# McPiFace-Camera-V1.net
KiCad netlist of a schematic drawn in EAGLE
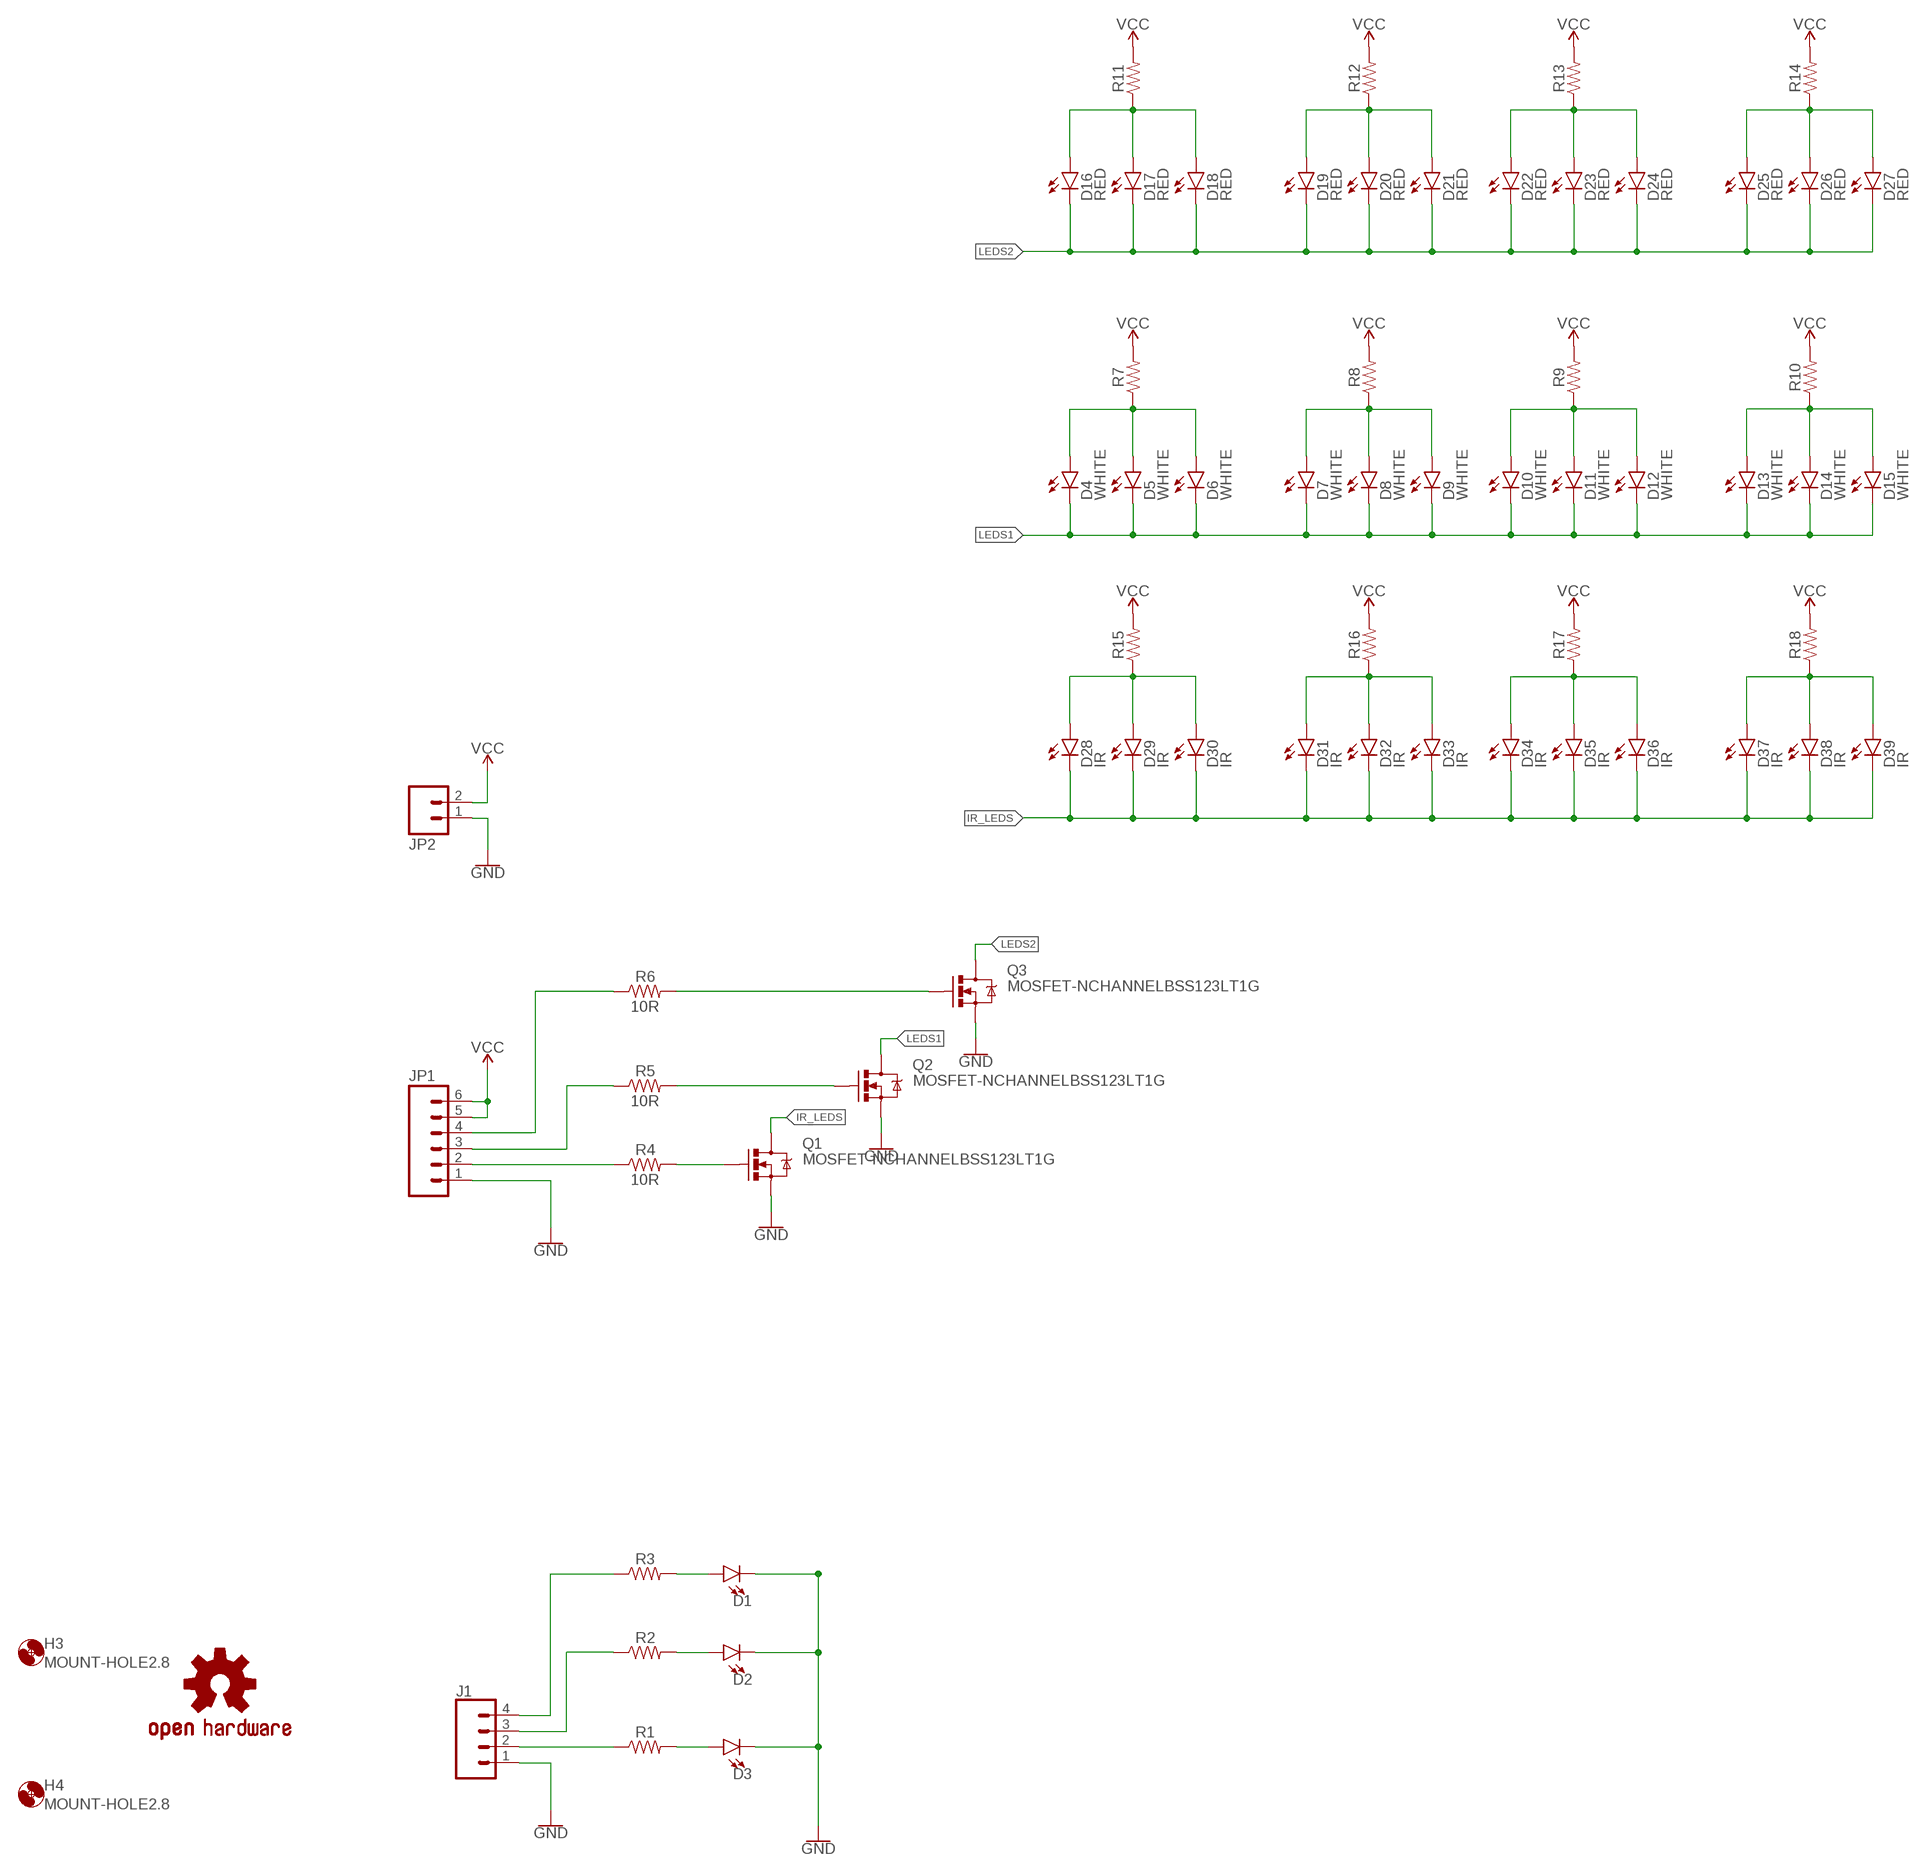
[diagram p0: schematic, sheet 1]

(export (version "E")
  (design (tool "Eeschema 10.0.6"))
  (components
    (comp (ref "D1")
      (value "LED1206-BOTTOM-1.6MM")
      (footprint "eagle-import:LED-1206-BOTTOM-1.6MM")
      (libsource (lib "eagle-import") (part "LED1206-BOTTOM-1.6MM"))
    )
    (comp (ref "D2")
      (value "LED1206-BOTTOM-1.6MM")
      (footprint "eagle-import:LED-1206-BOTTOM-1.6MM")
      (libsource (lib "eagle-import") (part "LED1206-BOTTOM-1.6MM"))
    )
    (comp (ref "D3")
      (value "LED1206-BOTTOM-1.6MM")
      (footprint "eagle-import:LED-1206-BOTTOM-1.6MM")
      (libsource (lib "eagle-import") (part "LED1206-BOTTOM-1.6MM"))
    )
    (comp (ref "D4")
      (value "WHITE")
      (footprint "eagle-import:LED-1206")
      (libsource (lib "eagle-import") (part "LED-WHITE1206"))
    )
    (comp (ref "D5")
      (value "WHITE")
      (footprint "eagle-import:LED-1206")
      (libsource (lib "eagle-import") (part "LED-WHITE1206"))
    )
    (comp (ref "D6")
      (value "WHITE")
      (footprint "eagle-import:LED-1206")
      (libsource (lib "eagle-import") (part "LED-WHITE1206"))
    )
    (comp (ref "D7")
      (value "WHITE")
      (footprint "eagle-import:LED-1206")
      (libsource (lib "eagle-import") (part "LED-WHITE1206"))
    )
    (comp (ref "D8")
      (value "WHITE")
      (footprint "eagle-import:LED-1206")
      (libsource (lib "eagle-import") (part "LED-WHITE1206"))
    )
    (comp (ref "D9")
      (value "WHITE")
      (footprint "eagle-import:LED-1206")
      (libsource (lib "eagle-import") (part "LED-WHITE1206"))
    )
    (comp (ref "D10")
      (value "WHITE")
      (footprint "eagle-import:LED-1206")
      (libsource (lib "eagle-import") (part "LED-WHITE1206"))
    )
    (comp (ref "D11")
      (value "WHITE")
      (footprint "eagle-import:LED-1206")
      (libsource (lib "eagle-import") (part "LED-WHITE1206"))
    )
    (comp (ref "D12")
      (value "WHITE")
      (footprint "eagle-import:LED-1206")
      (libsource (lib "eagle-import") (part "LED-WHITE1206"))
    )
    (comp (ref "D13")
      (value "WHITE")
      (footprint "eagle-import:LED-1206")
      (libsource (lib "eagle-import") (part "LED-WHITE1206"))
    )
    (comp (ref "D14")
      (value "WHITE")
      (footprint "eagle-import:LED-1206")
      (libsource (lib "eagle-import") (part "LED-WHITE1206"))
    )
    (comp (ref "D15")
      (value "WHITE")
      (footprint "eagle-import:LED-1206")
      (libsource (lib "eagle-import") (part "LED-WHITE1206"))
    )
    (comp (ref "D16")
      (value "RED")
      (footprint "eagle-import:LED-1206")
      (libsource (lib "eagle-import") (part "LED-RED1206"))
    )
    (comp (ref "D17")
      (value "RED")
      (footprint "eagle-import:LED-1206")
      (libsource (lib "eagle-import") (part "LED-RED1206"))
    )
    (comp (ref "D18")
      (value "RED")
      (footprint "eagle-import:LED-1206")
      (libsource (lib "eagle-import") (part "LED-RED1206"))
    )
    (comp (ref "D19")
      (value "RED")
      (footprint "eagle-import:LED-1206")
      (libsource (lib "eagle-import") (part "LED-RED1206"))
    )
    (comp (ref "D20")
      (value "RED")
      (footprint "eagle-import:LED-1206")
      (libsource (lib "eagle-import") (part "LED-RED1206"))
    )
    (comp (ref "D21")
      (value "RED")
      (footprint "eagle-import:LED-1206")
      (libsource (lib "eagle-import") (part "LED-RED1206"))
    )
    (comp (ref "D22")
      (value "RED")
      (footprint "eagle-import:LED-1206")
      (libsource (lib "eagle-import") (part "LED-RED1206"))
    )
    (comp (ref "D23")
      (value "RED")
      (footprint "eagle-import:LED-1206")
      (libsource (lib "eagle-import") (part "LED-RED1206"))
    )
    (comp (ref "D24")
      (value "RED")
      (footprint "eagle-import:LED-1206")
      (libsource (lib "eagle-import") (part "LED-RED1206"))
    )
    (comp (ref "D25")
      (value "RED")
      (footprint "eagle-import:LED-1206")
      (libsource (lib "eagle-import") (part "LED-RED1206"))
    )
    (comp (ref "D26")
      (value "RED")
      (footprint "eagle-import:LED-1206")
      (libsource (lib "eagle-import") (part "LED-RED1206"))
    )
    (comp (ref "D27")
      (value "RED")
      (footprint "eagle-import:LED-1206")
      (libsource (lib "eagle-import") (part "LED-RED1206"))
    )
    (comp (ref "D28")
      (value "IR")
      (footprint "eagle-import:LED-1206")
      (libsource (lib "eagle-import") (part "LED1206"))
    )
    (comp (ref "D29")
      (value "IR")
      (footprint "eagle-import:LED-1206")
      (libsource (lib "eagle-import") (part "LED1206"))
    )
    (comp (ref "D30")
      (value "IR")
      (footprint "eagle-import:LED-1206")
      (libsource (lib "eagle-import") (part "LED1206"))
    )
    (comp (ref "D31")
      (value "IR")
      (footprint "eagle-import:LED-1206")
      (libsource (lib "eagle-import") (part "LED1206"))
    )
    (comp (ref "D32")
      (value "IR")
      (footprint "eagle-import:LED-1206")
      (libsource (lib "eagle-import") (part "LED1206"))
    )
    (comp (ref "D33")
      (value "IR")
      (footprint "eagle-import:LED-1206")
      (libsource (lib "eagle-import") (part "LED1206"))
    )
    (comp (ref "D34")
      (value "IR")
      (footprint "eagle-import:LED-1206")
      (libsource (lib "eagle-import") (part "LED1206"))
    )
    (comp (ref "D35")
      (value "IR")
      (footprint "eagle-import:LED-1206")
      (libsource (lib "eagle-import") (part "LED1206"))
    )
    (comp (ref "D36")
      (value "IR")
      (footprint "eagle-import:LED-1206")
      (libsource (lib "eagle-import") (part "LED1206"))
    )
    (comp (ref "D37")
      (value "IR")
      (footprint "eagle-import:LED-1206")
      (libsource (lib "eagle-import") (part "LED1206"))
    )
    (comp (ref "D38")
      (value "IR")
      (footprint "eagle-import:LED-1206")
      (libsource (lib "eagle-import") (part "LED1206"))
    )
    (comp (ref "D39")
      (value "IR")
      (footprint "eagle-import:LED-1206")
      (libsource (lib "eagle-import") (part "LED1206"))
    )
    (comp (ref "H3")
      (value "MOUNT-HOLE2.8")
      (footprint "eagle-import:2,8")
      (libsource (lib "eagle-import") (part "MOUNT-HOLE2.8"))
    )
    (comp (ref "H4")
      (value "MOUNT-HOLE2.8")
      (footprint "eagle-import:2,8")
      (libsource (lib "eagle-import") (part "MOUNT-HOLE2.8"))
    )
    (comp (ref "J1")
      (value "CONN_04SMD2")
      (footprint "eagle-import:1X04_1MM_RA")
      (libsource (lib "eagle-import") (part "CONN_04SMD2"))
    )
    (comp (ref "JP1")
      (value "M06SMD-1MM")
      (footprint "eagle-import:1X06-1MM")
      (libsource (lib "eagle-import") (part "M06SMD-1MM"))
    )
    (comp (ref "JP2")
      (value "M02-JST-2MM-SMT")
      (footprint "eagle-import:JST-2-SMD")
      (libsource (lib "eagle-import") (part "M02-JST-2MM-SMT"))
    )
    (comp (ref "LOGO1")
      (value "OSHW-LOGOL")
      (footprint "eagle-import:OSHW-LOGO-L")
      (libsource (lib "eagle-import") (part "OSHW-LOGOL"))
    )
    (comp (ref "Q1")
      (value "MOSFET-NCHANNELBSS123LT1G")
      (footprint "eagle-import:SOT23-3")
      (libsource (lib "eagle-import") (part "MOSFET-NCHANNELBSS123LT1G"))
    )
    (comp (ref "Q2")
      (value "MOSFET-NCHANNELBSS123LT1G")
      (footprint "eagle-import:SOT23-3")
      (libsource (lib "eagle-import") (part "MOSFET-NCHANNELBSS123LT1G"))
    )
    (comp (ref "Q3")
      (value "MOSFET-NCHANNELBSS123LT1G")
      (footprint "eagle-import:SOT23-3")
      (libsource (lib "eagle-import") (part "MOSFET-NCHANNELBSS123LT1G"))
    )
    (comp (ref "R1")
      (value "RESISTOR1206")
      (footprint "eagle-import:1206")
      (libsource (lib "eagle-import") (part "RESISTOR1206"))
    )
    (comp (ref "R2")
      (value "RESISTOR1206")
      (footprint "eagle-import:1206")
      (libsource (lib "eagle-import") (part "RESISTOR1206"))
    )
    (comp (ref "R3")
      (value "RESISTOR1206")
      (footprint "eagle-import:1206")
      (libsource (lib "eagle-import") (part "RESISTOR1206"))
    )
    (comp (ref "R4")
      (value "10R")
      (footprint "eagle-import:1206")
      (libsource (lib "eagle-import") (part "RESISTOR1206"))
    )
    (comp (ref "R5")
      (value "10R")
      (footprint "eagle-import:1206")
      (libsource (lib "eagle-import") (part "RESISTOR1206"))
    )
    (comp (ref "R6")
      (value "10R")
      (footprint "eagle-import:1206")
      (libsource (lib "eagle-import") (part "RESISTOR1206"))
    )
    (comp (ref "R7")
      (value "RESISTOR1206")
      (footprint "eagle-import:1206")
      (libsource (lib "eagle-import") (part "RESISTOR1206"))
    )
    (comp (ref "R8")
      (value "RESISTOR1206")
      (footprint "eagle-import:1206")
      (libsource (lib "eagle-import") (part "RESISTOR1206"))
    )
    (comp (ref "R9")
      (value "RESISTOR1206")
      (footprint "eagle-import:1206")
      (libsource (lib "eagle-import") (part "RESISTOR1206"))
    )
    (comp (ref "R10")
      (value "RESISTOR1206")
      (footprint "eagle-import:1206")
      (libsource (lib "eagle-import") (part "RESISTOR1206"))
    )
    (comp (ref "R11")
      (value "RESISTOR1206")
      (footprint "eagle-import:1206")
      (libsource (lib "eagle-import") (part "RESISTOR1206"))
    )
    (comp (ref "R12")
      (value "RESISTOR1206")
      (footprint "eagle-import:1206")
      (libsource (lib "eagle-import") (part "RESISTOR1206"))
    )
    (comp (ref "R13")
      (value "RESISTOR1206")
      (footprint "eagle-import:1206")
      (libsource (lib "eagle-import") (part "RESISTOR1206"))
    )
    (comp (ref "R14")
      (value "RESISTOR1206")
      (footprint "eagle-import:1206")
      (libsource (lib "eagle-import") (part "RESISTOR1206"))
    )
    (comp (ref "R15")
      (value "RESISTOR1206")
      (footprint "eagle-import:1206")
      (libsource (lib "eagle-import") (part "RESISTOR1206"))
    )
    (comp (ref "R16")
      (value "RESISTOR1206")
      (footprint "eagle-import:1206")
      (libsource (lib "eagle-import") (part "RESISTOR1206"))
    )
    (comp (ref "R17")
      (value "RESISTOR1206")
      (footprint "eagle-import:1206")
      (libsource (lib "eagle-import") (part "RESISTOR1206"))
    )
    (comp (ref "R18")
      (value "RESISTOR1206")
      (footprint "eagle-import:1206")
      (libsource (lib "eagle-import") (part "RESISTOR1206"))
    )
  )
  (nets
    (net (code "1") (name "GND") (class "Default")
      (node (ref "D1") (pin "C") (pinfunction "C_C") (pintype "passive"))
      (node (ref "D2") (pin "C") (pinfunction "C_C") (pintype "passive"))
      (node (ref "D3") (pin "C") (pinfunction "C_C") (pintype "passive"))
      (node (ref "J1") (pin "1") (pinfunction "1_1") (pintype "passive"))
      (node (ref "JP1") (pin "1") (pinfunction "1_1") (pintype "passive"))
      (node (ref "JP2") (pin "1") (pinfunction "2_1") (pintype "passive"))
      (node (ref "Q1") (pin "2") (pinfunction "S_2") (pintype "passive"))
      (node (ref "Q2") (pin "2") (pinfunction "S_2") (pintype "passive"))
      (node (ref "Q3") (pin "2") (pinfunction "S_2") (pintype "passive"))
    )
    (net (code "2") (name "IR_LEDS") (class "Default")
      (node (ref "D28") (pin "C") (pinfunction "C_C") (pintype "passive"))
      (node (ref "D29") (pin "C") (pinfunction "C_C") (pintype "passive"))
      (node (ref "D30") (pin "C") (pinfunction "C_C") (pintype "passive"))
      (node (ref "D31") (pin "C") (pinfunction "C_C") (pintype "passive"))
      (node (ref "D32") (pin "C") (pinfunction "C_C") (pintype "passive"))
      (node (ref "D33") (pin "C") (pinfunction "C_C") (pintype "passive"))
      (node (ref "D34") (pin "C") (pinfunction "C_C") (pintype "passive"))
      (node (ref "D35") (pin "C") (pinfunction "C_C") (pintype "passive"))
      (node (ref "D36") (pin "C") (pinfunction "C_C") (pintype "passive"))
      (node (ref "D37") (pin "C") (pinfunction "C_C") (pintype "passive"))
      (node (ref "D38") (pin "C") (pinfunction "C_C") (pintype "passive"))
      (node (ref "D39") (pin "C") (pinfunction "C_C") (pintype "passive"))
      (node (ref "Q1") (pin "3") (pinfunction "D_3") (pintype "passive"))
    )
    (net (code "3") (name "LEDS1") (class "Default")
      (node (ref "D10") (pin "C") (pinfunction "C_C") (pintype "passive"))
      (node (ref "D11") (pin "C") (pinfunction "C_C") (pintype "passive"))
      (node (ref "D12") (pin "C") (pinfunction "C_C") (pintype "passive"))
      (node (ref "D13") (pin "C") (pinfunction "C_C") (pintype "passive"))
      (node (ref "D14") (pin "C") (pinfunction "C_C") (pintype "passive"))
      (node (ref "D15") (pin "C") (pinfunction "C_C") (pintype "passive"))
      (node (ref "D4") (pin "C") (pinfunction "C_C") (pintype "passive"))
      (node (ref "D5") (pin "C") (pinfunction "C_C") (pintype "passive"))
      (node (ref "D6") (pin "C") (pinfunction "C_C") (pintype "passive"))
      (node (ref "D7") (pin "C") (pinfunction "C_C") (pintype "passive"))
      (node (ref "D8") (pin "C") (pinfunction "C_C") (pintype "passive"))
      (node (ref "D9") (pin "C") (pinfunction "C_C") (pintype "passive"))
      (node (ref "Q2") (pin "3") (pinfunction "D_3") (pintype "passive"))
    )
    (net (code "4") (name "LEDS2") (class "Default")
      (node (ref "D16") (pin "C") (pinfunction "C_C") (pintype "passive"))
      (node (ref "D17") (pin "C") (pinfunction "C_C") (pintype "passive"))
      (node (ref "D18") (pin "C") (pinfunction "C_C") (pintype "passive"))
      (node (ref "D19") (pin "C") (pinfunction "C_C") (pintype "passive"))
      (node (ref "D20") (pin "C") (pinfunction "C_C") (pintype "passive"))
      (node (ref "D21") (pin "C") (pinfunction "C_C") (pintype "passive"))
      (node (ref "D22") (pin "C") (pinfunction "C_C") (pintype "passive"))
      (node (ref "D23") (pin "C") (pinfunction "C_C") (pintype "passive"))
      (node (ref "D24") (pin "C") (pinfunction "C_C") (pintype "passive"))
      (node (ref "D25") (pin "C") (pinfunction "C_C") (pintype "passive"))
      (node (ref "D26") (pin "C") (pinfunction "C_C") (pintype "passive"))
      (node (ref "D27") (pin "C") (pinfunction "C_C") (pintype "passive"))
      (node (ref "Q3") (pin "3") (pinfunction "D_3") (pintype "passive"))
    )
    (net (code "5") (name "Net-(D1-PadA)") (class "Default")
      (node (ref "D1") (pin "A") (pinfunction "A_A") (pintype "passive"))
      (node (ref "R3") (pin "2") (pinfunction "2_2") (pintype "passive"))
    )
    (net (code "6") (name "Net-(D2-PadA)") (class "Default")
      (node (ref "D2") (pin "A") (pinfunction "A_A") (pintype "passive"))
      (node (ref "R2") (pin "2") (pinfunction "2_2") (pintype "passive"))
    )
    (net (code "7") (name "Net-(D3-PadA)") (class "Default")
      (node (ref "D3") (pin "A") (pinfunction "A_A") (pintype "passive"))
      (node (ref "R1") (pin "2") (pinfunction "2_2") (pintype "passive"))
    )
    (net (code "8") (name "Net-(D4-PadA)") (class "Default")
      (node (ref "D4") (pin "A") (pinfunction "A_A") (pintype "passive"))
      (node (ref "D5") (pin "A") (pinfunction "A_A") (pintype "passive"))
      (node (ref "D6") (pin "A") (pinfunction "A_A") (pintype "passive"))
      (node (ref "R7") (pin "1") (pinfunction "1_1") (pintype "passive"))
    )
    (net (code "9") (name "Net-(D7-PadA)") (class "Default")
      (node (ref "D7") (pin "A") (pinfunction "A_A") (pintype "passive"))
      (node (ref "D8") (pin "A") (pinfunction "A_A") (pintype "passive"))
      (node (ref "D9") (pin "A") (pinfunction "A_A") (pintype "passive"))
      (node (ref "R8") (pin "1") (pinfunction "1_1") (pintype "passive"))
    )
    (net (code "10") (name "Net-(D10-PadA)") (class "Default")
      (node (ref "D10") (pin "A") (pinfunction "A_A") (pintype "passive"))
      (node (ref "D11") (pin "A") (pinfunction "A_A") (pintype "passive"))
      (node (ref "D12") (pin "A") (pinfunction "A_A") (pintype "passive"))
      (node (ref "R9") (pin "1") (pinfunction "1_1") (pintype "passive"))
    )
    (net (code "11") (name "Net-(D13-PadA)") (class "Default")
      (node (ref "D13") (pin "A") (pinfunction "A_A") (pintype "passive"))
      (node (ref "D14") (pin "A") (pinfunction "A_A") (pintype "passive"))
      (node (ref "D15") (pin "A") (pinfunction "A_A") (pintype "passive"))
      (node (ref "R10") (pin "1") (pinfunction "1_1") (pintype "passive"))
    )
    (net (code "12") (name "Net-(D16-PadA)") (class "Default")
      (node (ref "D16") (pin "A") (pinfunction "A_A") (pintype "passive"))
      (node (ref "D17") (pin "A") (pinfunction "A_A") (pintype "passive"))
      (node (ref "D18") (pin "A") (pinfunction "A_A") (pintype "passive"))
      (node (ref "R11") (pin "1") (pinfunction "1_1") (pintype "passive"))
    )
    (net (code "13") (name "Net-(D19-PadA)") (class "Default")
      (node (ref "D19") (pin "A") (pinfunction "A_A") (pintype "passive"))
      (node (ref "D20") (pin "A") (pinfunction "A_A") (pintype "passive"))
      (node (ref "D21") (pin "A") (pinfunction "A_A") (pintype "passive"))
      (node (ref "R12") (pin "1") (pinfunction "1_1") (pintype "passive"))
    )
    (net (code "14") (name "Net-(D22-PadA)") (class "Default")
      (node (ref "D22") (pin "A") (pinfunction "A_A") (pintype "passive"))
      (node (ref "D23") (pin "A") (pinfunction "A_A") (pintype "passive"))
      (node (ref "D24") (pin "A") (pinfunction "A_A") (pintype "passive"))
      (node (ref "R13") (pin "1") (pinfunction "1_1") (pintype "passive"))
    )
    (net (code "15") (name "Net-(D25-PadA)") (class "Default")
      (node (ref "D25") (pin "A") (pinfunction "A_A") (pintype "passive"))
      (node (ref "D26") (pin "A") (pinfunction "A_A") (pintype "passive"))
      (node (ref "D27") (pin "A") (pinfunction "A_A") (pintype "passive"))
      (node (ref "R14") (pin "1") (pinfunction "1_1") (pintype "passive"))
    )
    (net (code "16") (name "Net-(D28-PadA)") (class "Default")
      (node (ref "D28") (pin "A") (pinfunction "A_A") (pintype "passive"))
      (node (ref "D29") (pin "A") (pinfunction "A_A") (pintype "passive"))
      (node (ref "D30") (pin "A") (pinfunction "A_A") (pintype "passive"))
      (node (ref "R15") (pin "1") (pinfunction "1_1") (pintype "passive"))
    )
    (net (code "17") (name "Net-(D31-PadA)") (class "Default")
      (node (ref "D31") (pin "A") (pinfunction "A_A") (pintype "passive"))
      (node (ref "D32") (pin "A") (pinfunction "A_A") (pintype "passive"))
      (node (ref "D33") (pin "A") (pinfunction "A_A") (pintype "passive"))
      (node (ref "R16") (pin "1") (pinfunction "1_1") (pintype "passive"))
    )
    (net (code "18") (name "Net-(D34-PadA)") (class "Default")
      (node (ref "D34") (pin "A") (pinfunction "A_A") (pintype "passive"))
      (node (ref "D35") (pin "A") (pinfunction "A_A") (pintype "passive"))
      (node (ref "D36") (pin "A") (pinfunction "A_A") (pintype "passive"))
      (node (ref "R17") (pin "1") (pinfunction "1_1") (pintype "passive"))
    )
    (net (code "19") (name "Net-(D37-PadA)") (class "Default")
      (node (ref "D37") (pin "A") (pinfunction "A_A") (pintype "passive"))
      (node (ref "D38") (pin "A") (pinfunction "A_A") (pintype "passive"))
      (node (ref "D39") (pin "A") (pinfunction "A_A") (pintype "passive"))
      (node (ref "R18") (pin "1") (pinfunction "1_1") (pintype "passive"))
    )
    (net (code "20") (name "Net-(J1-Pad2)") (class "Default")
      (node (ref "J1") (pin "2") (pinfunction "2_2") (pintype "passive"))
      (node (ref "R1") (pin "1") (pinfunction "1_1") (pintype "passive"))
    )
    (net (code "21") (name "Net-(J1-Pad3)") (class "Default")
      (node (ref "J1") (pin "3") (pinfunction "3_3") (pintype "passive"))
      (node (ref "R2") (pin "1") (pinfunction "1_1") (pintype "passive"))
    )
    (net (code "22") (name "Net-(J1-Pad4)") (class "Default")
      (node (ref "J1") (pin "4") (pinfunction "4_4") (pintype "passive"))
      (node (ref "R3") (pin "1") (pinfunction "1_1") (pintype "passive"))
    )
    (net (code "23") (name "Net-(JP1-Pad2)") (class "Default")
      (node (ref "JP1") (pin "2") (pinfunction "2_2") (pintype "passive"))
      (node (ref "R4") (pin "1") (pinfunction "1_1") (pintype "passive"))
    )
    (net (code "24") (name "Net-(JP1-Pad3)") (class "Default")
      (node (ref "JP1") (pin "3") (pinfunction "3_3") (pintype "passive"))
      (node (ref "R5") (pin "1") (pinfunction "1_1") (pintype "passive"))
    )
    (net (code "25") (name "Net-(JP1-Pad4)") (class "Default")
      (node (ref "JP1") (pin "4") (pinfunction "4_4") (pintype "passive"))
      (node (ref "R6") (pin "1") (pinfunction "1_1") (pintype "passive"))
    )
    (net (code "26") (name "Net-(Q1-G)") (class "Default")
      (node (ref "Q1") (pin "1") (pinfunction "G_1") (pintype "passive"))
      (node (ref "R4") (pin "2") (pinfunction "2_2") (pintype "passive"))
    )
    (net (code "27") (name "Net-(Q2-G)") (class "Default")
      (node (ref "Q2") (pin "1") (pinfunction "G_1") (pintype "passive"))
      (node (ref "R5") (pin "2") (pinfunction "2_2") (pintype "passive"))
    )
    (net (code "28") (name "Net-(Q3-G)") (class "Default")
      (node (ref "Q3") (pin "1") (pinfunction "G_1") (pintype "passive"))
      (node (ref "R6") (pin "2") (pinfunction "2_2") (pintype "passive"))
    )
    (net (code "29") (name "VCC") (class "Default")
      (node (ref "JP1") (pin "5") (pinfunction "5_5") (pintype "passive"))
      (node (ref "JP1") (pin "6") (pinfunction "6_6") (pintype "passive"))
      (node (ref "JP2") (pin "2") (pinfunction "1_2") (pintype "passive"))
      (node (ref "R10") (pin "2") (pinfunction "2_2") (pintype "passive"))
      (node (ref "R11") (pin "2") (pinfunction "2_2") (pintype "passive"))
      (node (ref "R12") (pin "2") (pinfunction "2_2") (pintype "passive"))
      (node (ref "R13") (pin "2") (pinfunction "2_2") (pintype "passive"))
      (node (ref "R14") (pin "2") (pinfunction "2_2") (pintype "passive"))
      (node (ref "R15") (pin "2") (pinfunction "2_2") (pintype "passive"))
      (node (ref "R16") (pin "2") (pinfunction "2_2") (pintype "passive"))
      (node (ref "R17") (pin "2") (pinfunction "2_2") (pintype "passive"))
      (node (ref "R18") (pin "2") (pinfunction "2_2") (pintype "passive"))
      (node (ref "R7") (pin "2") (pinfunction "2_2") (pintype "passive"))
      (node (ref "R8") (pin "2") (pinfunction "2_2") (pintype "passive"))
      (node (ref "R9") (pin "2") (pinfunction "2_2") (pintype "passive"))
    )
  )
)
